# BMP388.net
KiCad netlist of a schematic drawn in Altium Designer
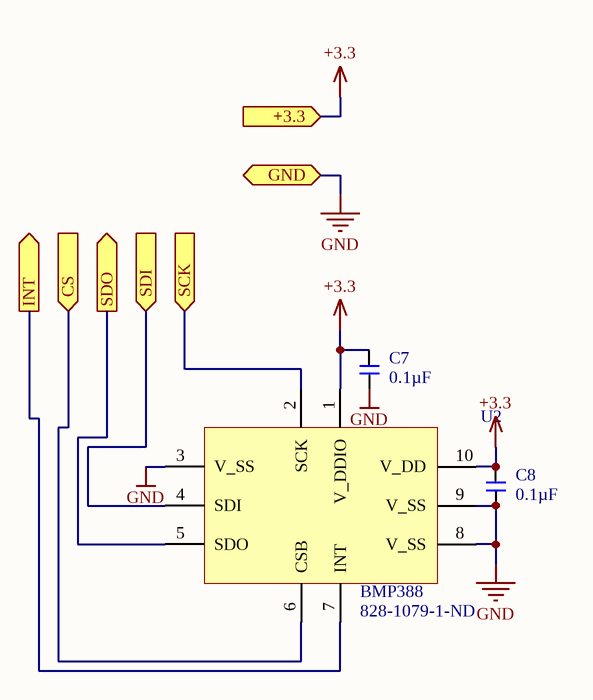
[diagram p0: BMP388.SchDoc]

(export (version "E")
  (design (tool "Eeschema 10.0.6"))
  (components
    (comp (ref "C7")
      (value "__template_cap")
      (footprint "C0603")
      (fields
        (field (name "CAPACITANCE (SHORTHAND)") "0.1µF")
        (field (name "MANUFACTURER") "Murata Electronics North America")
      )
      (libsource (lib "passives") (part "__template_cap"))
    )
    (comp (ref "C8")
      (value "__template_cap")
      (footprint "C0603")
      (fields
        (field (name "CAPACITANCE (SHORTHAND)") "0.1µF")
        (field (name "MANUFACTURER") "Murata Electronics North America")
      )
      (libsource (lib "passives") (part "__template_cap"))
    )
    (comp (ref "U2")
      (value "BMP388")
      (footprint "8 pin LGA")
      (description "Pressure Sensor 4.35 PSI ~ 18.13 PSI (30 kPa ~ 125 kPa) Absolute 10-WFLGA")
      (fields
        (field (name "MANUFACTURER") "Bosch Sensortec")
        (field (name "SUPPLIER PART NUMBER 1") "828-1079-1-ND")
      )
      (libsource (lib "SSI") (part "BMP388"))
    )
  )
  (nets
    (net (code "1") (name "+3.3") (class "Default")
      (node (ref "C7") (pin "2") (pintype "passive"))
      (node (ref "C8") (pin "2") (pintype "passive"))
      (node (ref "U2") (pin "1") (pinfunction "V_DDIO_1") (pintype "passive"))
      (node (ref "U2") (pin "10") (pinfunction "V_DD_10") (pintype "passive"))
    )
    (net (code "2") (name "/CS") (class "Default")
      (node (ref "U2") (pin "6") (pinfunction "CSB_6") (pintype "passive"))
    )
    (net (code "3") (name "/INT") (class "Default")
      (node (ref "U2") (pin "7") (pinfunction "INT_7") (pintype "passive"))
    )
    (net (code "4") (name "/SCK") (class "Default")
      (node (ref "U2") (pin "2") (pinfunction "SCK_2") (pintype "passive"))
    )
    (net (code "5") (name "/SDI") (class "Default")
      (node (ref "U2") (pin "4") (pinfunction "SDI_4") (pintype "passive"))
    )
    (net (code "6") (name "/SDO") (class "Default")
      (node (ref "U2") (pin "5") (pinfunction "SDO_5") (pintype "passive"))
    )
    (net (code "7") (name "GND") (class "Default")
      (node (ref "C7") (pin "1") (pintype "passive"))
      (node (ref "C8") (pin "1") (pintype "passive"))
      (node (ref "U2") (pin "3") (pinfunction "V_SS_3") (pintype "passive"))
      (node (ref "U2") (pin "8") (pinfunction "V_SS_8") (pintype "passive"))
      (node (ref "U2") (pin "9") (pinfunction "V_SS_9") (pintype "passive"))
    )
  )
)
